# 02_-_MCU.net
KiCad netlist of a schematic drawn in Altium Designer
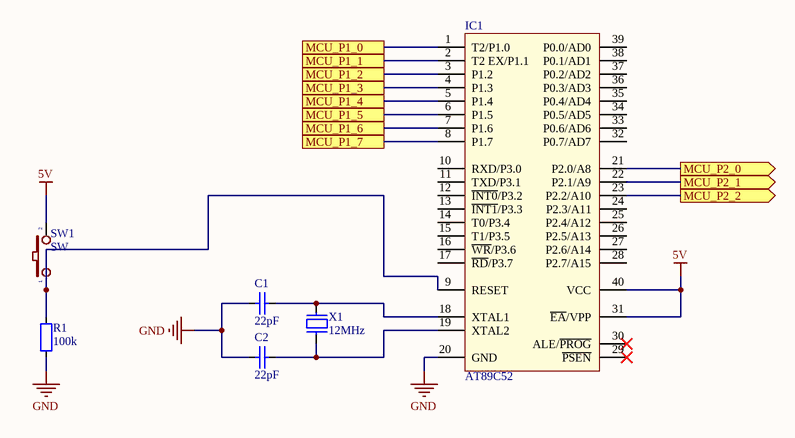
[diagram p0: [02] - MCU.SchDoc]

(export (version "E")
  (design (tool "Eeschema 10.0.6"))
  (components
    (comp (ref "C1")
      (value "22pF")
      (footprint "CAP_0805")
      (description "Capacitor")
      (fields (field (name "PUBLISHER") "Altium Limited"))
      (libsource (lib "My Library") (part "CapSMD"))
    )
    (comp (ref "C2")
      (value "22pF")
      (footprint "CAP_0805")
      (description "Capacitor")
      (fields (field (name "PUBLISHER") "Altium Limited"))
      (libsource (lib "My Library") (part "CapSMD"))
    )
    (comp (ref "IC1")
      (value "AT89C52")
      (footprint "DIP40/W0.6")
      (description "Atmel AT89C52, 8k Byte Flash Memory , 40 Pin")
      (libsource (lib "My Library") (part "AT89C52"))
    )
    (comp (ref "R1")
      (value "100k")
      (footprint "RES-SMD-0805")
      (description "Resistor")
      (fields
        (field (name "MANUFACTURER") "Generic Components")
        (field (name "PUBLISHER") "Altium Hobart Technology Centre")
      )
      (libsource (lib "My Library") (part "Resistor - SMD"))
    )
    (comp (ref "SW1")
      (value "SW")
      (footprint "SW2")
      (description "Switch button 2 pin")
      (libsource (lib "My Library") (part "SW2"))
    )
    (comp (ref "X1")
      (value "12MHz")
      (footprint "XT2")
      (description "Crystal For all Crystal 2pin.")
      (libsource (lib "My Library") (part "XT2"))
    )
  )
  (nets
    (net (code "1") (name "/MCU_P1_0") (class "Default")
      (node (ref "IC1") (pin "1") (pinfunction "T2/P1.0_1") (pintype "passive"))
    )
    (net (code "2") (name "/MCU_P1_1") (class "Default")
      (node (ref "IC1") (pin "2") (pinfunction "T2_EX/P1.1_2") (pintype "passive"))
    )
    (net (code "3") (name "/MCU_P1_2") (class "Default")
      (node (ref "IC1") (pin "3") (pinfunction "P1.2_3") (pintype "passive"))
    )
    (net (code "4") (name "/MCU_P1_3") (class "Default")
      (node (ref "IC1") (pin "4") (pinfunction "P1.3_4") (pintype "passive"))
    )
    (net (code "5") (name "/MCU_P1_4") (class "Default")
      (node (ref "IC1") (pin "5") (pinfunction "P1.4_5") (pintype "passive"))
    )
    (net (code "6") (name "/MCU_P1_5") (class "Default")
      (node (ref "IC1") (pin "6") (pinfunction "P1.5_6") (pintype "passive"))
    )
    (net (code "7") (name "/MCU_P1_6") (class "Default")
      (node (ref "IC1") (pin "7") (pinfunction "P1.6_7") (pintype "passive"))
    )
    (net (code "8") (name "/MCU_P1_7") (class "Default")
      (node (ref "IC1") (pin "8") (pinfunction "P1.7_8") (pintype "passive"))
    )
    (net (code "9") (name "/MCU_P2_0") (class "Default")
      (node (ref "IC1") (pin "21") (pinfunction "P2.0/A8_21") (pintype "passive"))
    )
    (net (code "10") (name "/MCU_P2_1") (class "Default")
      (node (ref "IC1") (pin "22") (pinfunction "P2.1/A9_22") (pintype "passive"))
    )
    (net (code "11") (name "/MCU_P2_2") (class "Default")
      (node (ref "IC1") (pin "23") (pinfunction "P2.2/A10_23") (pintype "passive"))
    )
    (net (code "12") (name "5V") (class "Default")
      (node (ref "IC1") (pin "31") (pinfunction "~{EA}/VPP_31") (pintype "passive"))
      (node (ref "IC1") (pin "40") (pinfunction "VCC_40") (pintype "power_in"))
      (node (ref "SW1") (pin "2") (pinfunction "2_2") (pintype "passive"))
    )
    (net (code "13") (name "GND") (class "Default")
      (node (ref "C1") (pin "1") (pinfunction "1_1") (pintype "passive"))
      (node (ref "C2") (pin "1") (pinfunction "1_1") (pintype "passive"))
      (node (ref "IC1") (pin "20") (pinfunction "GND_20") (pintype "open_emitter"))
      (node (ref "R1") (pin "1") (pinfunction "1_1") (pintype "passive"))
    )
    (net (code "14") (name "Net-(IC1-RESET)") (class "Default")
      (node (ref "IC1") (pin "9") (pinfunction "RESET_9") (pintype "passive"))
      (node (ref "R1") (pin "2") (pinfunction "2_2") (pintype "passive"))
      (node (ref "SW1") (pin "1") (pinfunction "1_1") (pintype "passive"))
    )
    (net (code "15") (name "Net-(IC1-XTAL1)") (class "Default")
      (node (ref "C1") (pin "2") (pinfunction "2_2") (pintype "passive"))
      (node (ref "IC1") (pin "18") (pinfunction "XTAL1_18") (pintype "passive"))
      (node (ref "X1") (pin "2") (pinfunction "2_2") (pintype "passive"))
    )
    (net (code "16") (name "Net-(IC1-XTAL2)") (class "Default")
      (node (ref "C2") (pin "2") (pinfunction "2_2") (pintype "passive"))
      (node (ref "IC1") (pin "19") (pinfunction "XTAL2_19") (pintype "passive"))
      (node (ref "X1") (pin "1") (pinfunction "1_1") (pintype "passive"))
    )
    (net (code "17") (name "unconnected-(IC1-ALE{slash}~{PROG}-Pad30)") (class "Default")
      (node (ref "IC1") (pin "30") (pinfunction "ALE/~{PROG}_30") (pintype "passive+no_connect"))
    )
    (net (code "18") (name "unconnected-(IC1-P0.0{slash}AD0-Pad39)") (class "Default")
      (node (ref "IC1") (pin "39") (pinfunction "P0.0/AD0_39") (pintype "passive"))
    )
    (net (code "19") (name "unconnected-(IC1-P0.1{slash}AD1-Pad38)") (class "Default")
      (node (ref "IC1") (pin "38") (pinfunction "P0.1/AD1_38") (pintype "passive"))
    )
    (net (code "20") (name "unconnected-(IC1-P0.2{slash}AD2-Pad37)") (class "Default")
      (node (ref "IC1") (pin "37") (pinfunction "P0.2/AD2_37") (pintype "passive"))
    )
    (net (code "21") (name "unconnected-(IC1-P0.3{slash}AD3-Pad36)") (class "Default")
      (node (ref "IC1") (pin "36") (pinfunction "P0.3/AD3_36") (pintype "passive"))
    )
    (net (code "22") (name "unconnected-(IC1-P0.4{slash}AD4-Pad35)") (class "Default")
      (node (ref "IC1") (pin "35") (pinfunction "P0.4/AD4_35") (pintype "passive"))
    )
    (net (code "23") (name "unconnected-(IC1-P0.5{slash}AD5-Pad34)") (class "Default")
      (node (ref "IC1") (pin "34") (pinfunction "P0.5/AD5_34") (pintype "passive"))
    )
    (net (code "24") (name "unconnected-(IC1-P0.6{slash}AD6-Pad33)") (class "Default")
      (node (ref "IC1") (pin "33") (pinfunction "P0.6/AD6_33") (pintype "passive"))
    )
    (net (code "25") (name "unconnected-(IC1-P0.7{slash}AD7-Pad32)") (class "Default")
      (node (ref "IC1") (pin "32") (pinfunction "P0.7/AD7_32") (pintype "passive"))
    )
    (net (code "26") (name "unconnected-(IC1-P2.3{slash}A11-Pad24)") (class "Default")
      (node (ref "IC1") (pin "24") (pinfunction "P2.3/A11_24") (pintype "passive"))
    )
    (net (code "27") (name "unconnected-(IC1-P2.4{slash}A12-Pad25)") (class "Default")
      (node (ref "IC1") (pin "25") (pinfunction "P2.4/A12_25") (pintype "passive"))
    )
    (net (code "28") (name "unconnected-(IC1-P2.5{slash}A13-Pad26)") (class "Default")
      (node (ref "IC1") (pin "26") (pinfunction "P2.5/A13_26") (pintype "passive"))
    )
    (net (code "29") (name "unconnected-(IC1-P2.6{slash}A14-Pad27)") (class "Default")
      (node (ref "IC1") (pin "27") (pinfunction "P2.6/A14_27") (pintype "passive"))
    )
    (net (code "30") (name "unconnected-(IC1-P2.7{slash}A15-Pad28)") (class "Default")
      (node (ref "IC1") (pin "28") (pinfunction "P2.7/A15_28") (pintype "passive"))
    )
    (net (code "31") (name "unconnected-(IC1-RXD{slash}P3.0-Pad10)") (class "Default")
      (node (ref "IC1") (pin "10") (pinfunction "RXD/P3.0_10") (pintype "passive"))
    )
    (net (code "32") (name "unconnected-(IC1-T0{slash}P3.4-Pad14)") (class "Default")
      (node (ref "IC1") (pin "14") (pinfunction "T0/P3.4_14") (pintype "passive"))
    )
    (net (code "33") (name "unconnected-(IC1-T1{slash}P3.5-Pad15)") (class "Default")
      (node (ref "IC1") (pin "15") (pinfunction "T1/P3.5_15") (pintype "passive"))
    )
    (net (code "34") (name "unconnected-(IC1-TXD{slash}P3.1-Pad11)") (class "Default")
      (node (ref "IC1") (pin "11") (pinfunction "TXD/P3.1_11") (pintype "passive"))
    )
    (net (code "35") (name "unconnected-(IC1-~{INT0}{slash}P3.2-Pad12)") (class "Default")
      (node (ref "IC1") (pin "12") (pinfunction "~{INT0}/P3.2_12") (pintype "passive"))
    )
    (net (code "36") (name "unconnected-(IC1-~{INT1}{slash}P3.3-Pad13)") (class "Default")
      (node (ref "IC1") (pin "13") (pinfunction "~{INT1}/P3.3_13") (pintype "passive"))
    )
    (net (code "37") (name "unconnected-(IC1-~{PSEN}-Pad29)") (class "Default")
      (node (ref "IC1") (pin "29") (pinfunction "~{PSEN}_29") (pintype "passive+no_connect"))
    )
    (net (code "38") (name "unconnected-(IC1-~{RD}{slash}P3.7-Pad17)") (class "Default")
      (node (ref "IC1") (pin "17") (pinfunction "~{RD}/P3.7_17") (pintype "passive"))
    )
    (net (code "39") (name "unconnected-(IC1-~{WR}{slash}P3.6-Pad16)") (class "Default")
      (node (ref "IC1") (pin "16") (pinfunction "~{WR}/P3.6_16") (pintype "passive"))
    )
  )
)
